# 06_-_Audio.net
KiCad netlist of a schematic drawn in Altium Designer
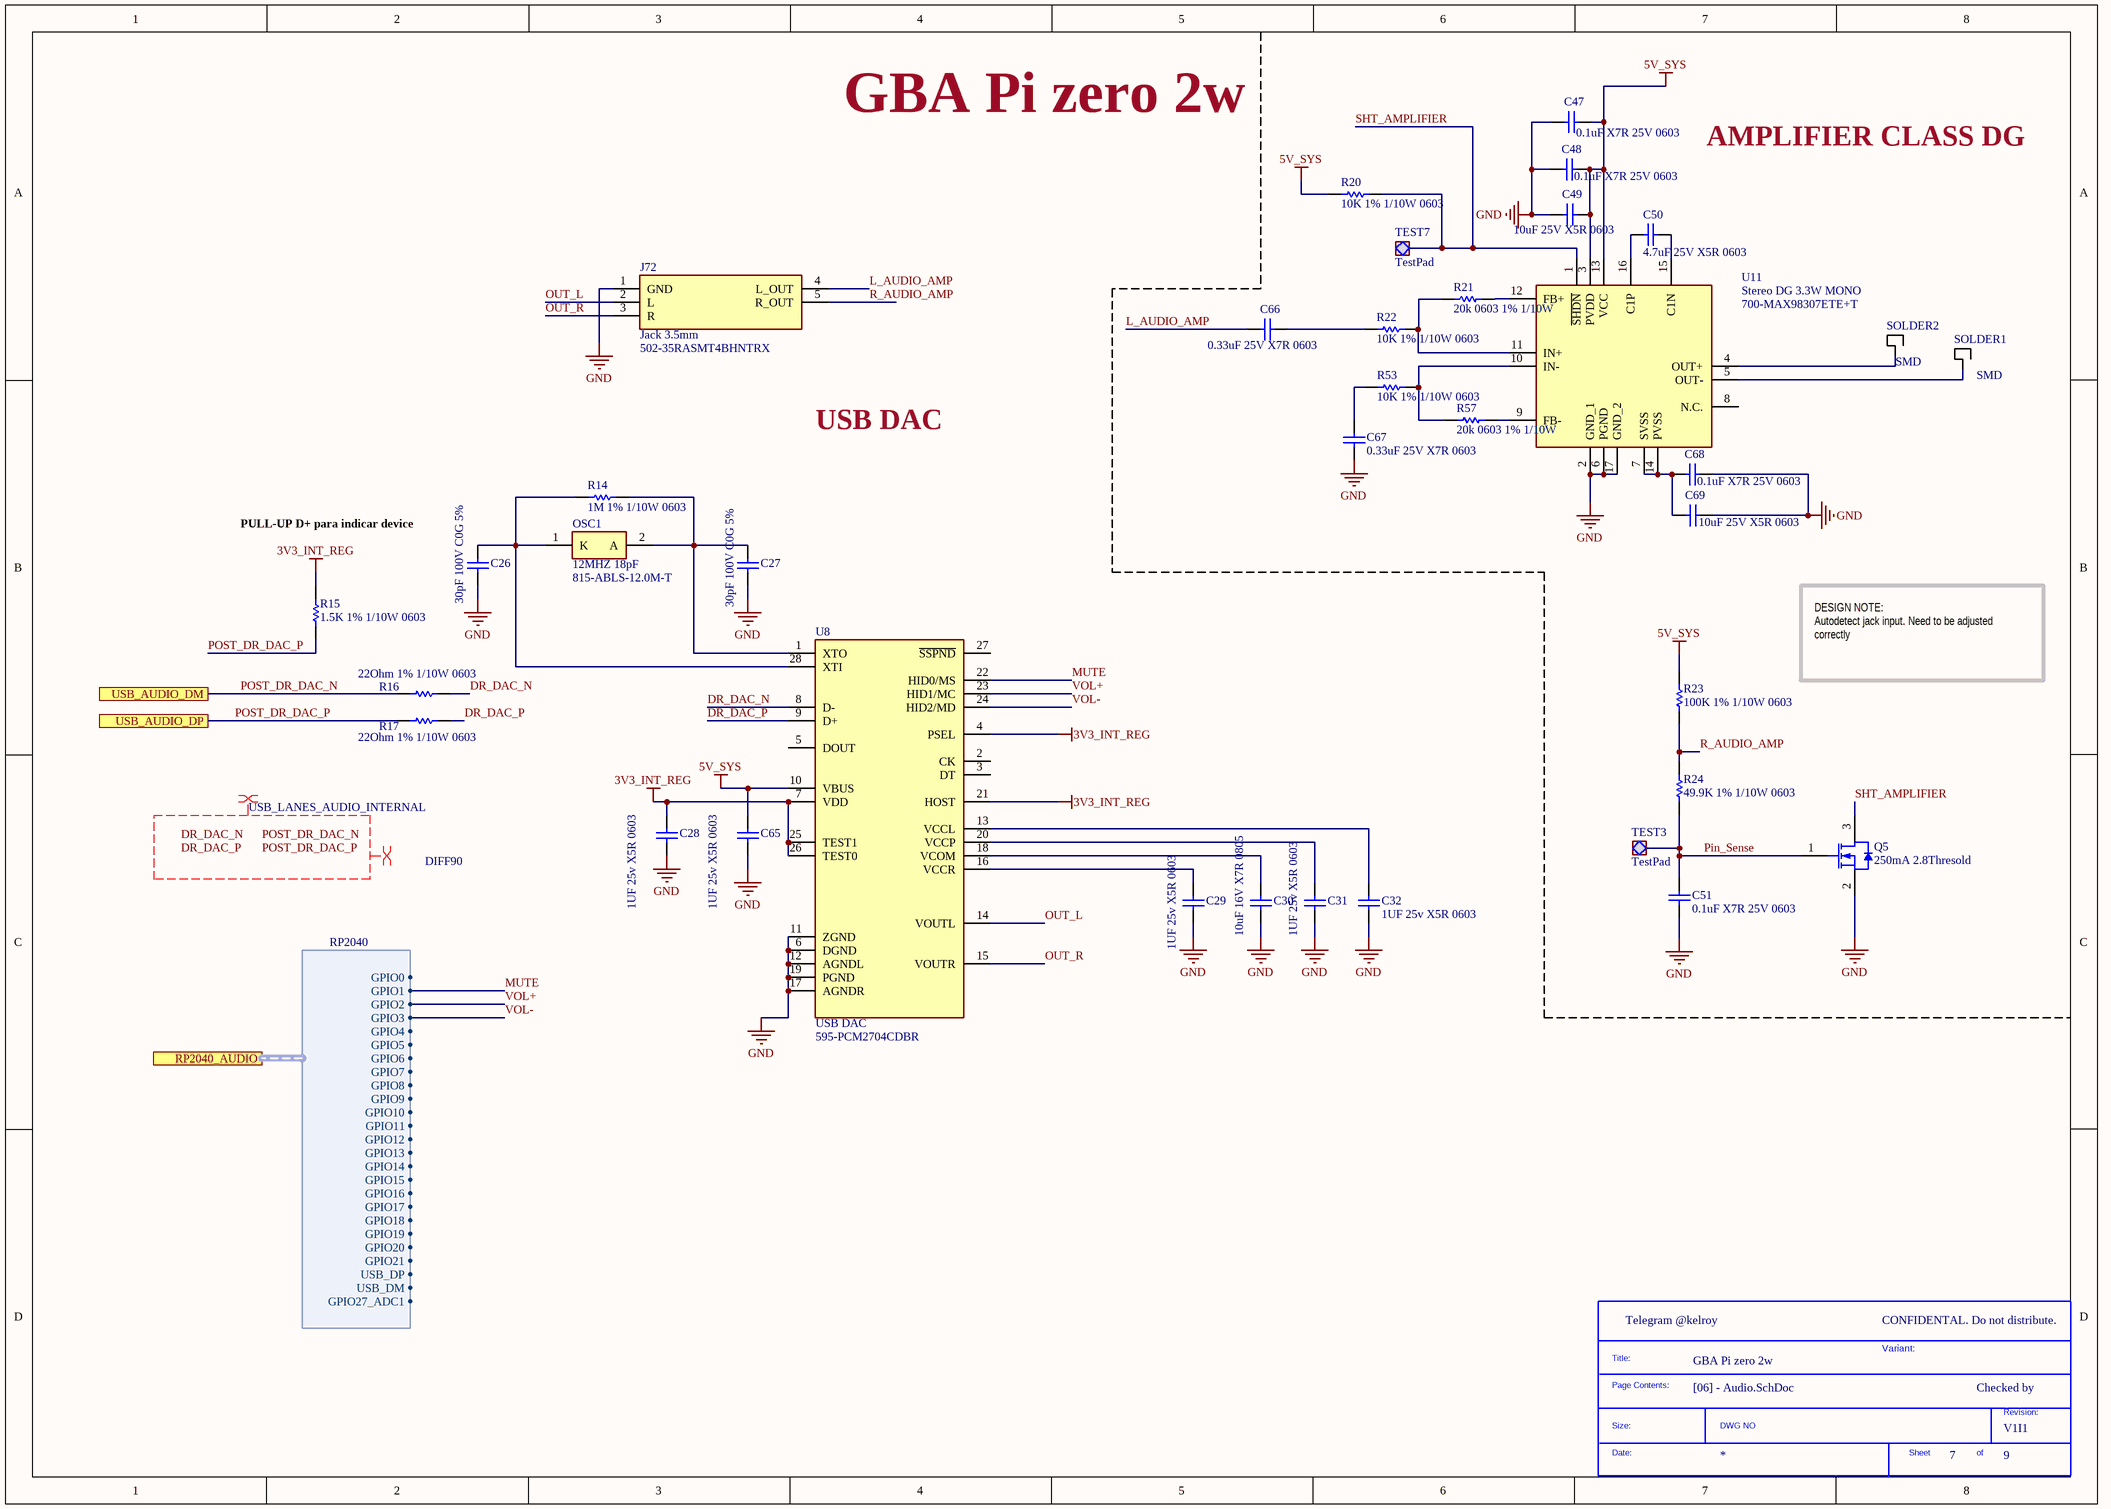
[diagram p0: [06] - Audio.SchDoc]

(export (version "E")
  (design (tool "Eeschema 10.0.6"))
  (components
    (comp (ref "C26")
      (value "30pF 100V C0G 5%")
      (footprint "C 0603/1608")
      (description "Condensadores de cerámica multicapa (MLCC- SMD/SMT) 30pF 100Volts C0G 5%")
      (fields
        (field (name "MANUFACTURER") "Murata")
        (field (name "MANUFACTURER PART NUMBER") "GCM1885C2A300JA16D")
      )
      (libsource (lib "LAN9514") (part "GCM1885C2A300JA16D"))
    )
    (comp (ref "C27")
      (value "30pF 100V C0G 5%")
      (footprint "C 0603/1608")
      (description "Condensadores de cerámica multicapa (MLCC- SMD/SMT) 30pF 100Volts C0G 5%")
      (fields
        (field (name "MANUFACTURER") "Murata")
        (field (name "MANUFACTURER PART NUMBER") "GCM1885C2A300JA16D")
      )
      (libsource (lib "LAN9514") (part "GCM1885C2A300JA16D"))
    )
    (comp (ref "C28")
      (value "1UF 25v X5R 0603")
      (footprint "C 0603/1608")
      (description "CAP CER 1UF 25V X5R 0603")
      (fields
        (field (name "MANUFACTURER") "Yageo")
        (field (name "MANUFACTURER PART NUMBER") "CC0603KRX5R8BB105")
      )
      (libsource (lib "CM3Board_V1I2") (part "CC0603KRX5R8BB105"))
    )
    (comp (ref "C29")
      (value "1UF 25v X5R 0603")
      (footprint "C 0603/1608")
      (description "CAP CER 1UF 25V X5R 0603")
      (fields
        (field (name "MANUFACTURER") "Yageo")
        (field (name "MANUFACTURER PART NUMBER") "CC0603KRX5R8BB105")
      )
      (libsource (lib "CM3Board_V1I2") (part "CC0603KRX5R8BB105"))
    )
    (comp (ref "C30")
      (value "10uF 16V X7R 0805")
      (footprint "C 0805/2012")
      (description "CAP CER 10UF 16V X7R 0805")
      (fields
        (field (name "MANUFACTURER") "Samsung Electro-Mechanics")
        (field (name "MANUFACTURER PART NUMBER") "CL21B106KOQNNNE")
      )
      (libsource (lib "CM3Board_V1I2") (part "CL21B106KOQNNNE"))
    )
    (comp (ref "C31")
      (value "1UF 25v X5R 0603")
      (footprint "C 0603/1608")
      (description "CAP CER 1UF 25V X5R 0603")
      (fields
        (field (name "MANUFACTURER") "Yageo")
        (field (name "MANUFACTURER PART NUMBER") "CC0603KRX5R8BB105")
      )
      (libsource (lib "CM3Board_V1I2") (part "CC0603KRX5R8BB105"))
    )
    (comp (ref "C32")
      (value "1UF 25v X5R 0603")
      (footprint "C 0603/1608")
      (description "CAP CER 1UF 25V X5R 0603")
      (fields
        (field (name "MANUFACTURER") "Yageo")
        (field (name "MANUFACTURER PART NUMBER") "CC0603KRX5R8BB105")
      )
      (libsource (lib "CM3Board_V1I2") (part "CC0603KRX5R8BB105"))
    )
    (comp (ref "C47")
      (value "0.1uF X7R 25V 0603")
      (footprint "C 0603/1608")
      (fields
        (field (name "MANUFACTURER") "Wurth Electronics")
        (field (name "MANUFACTURER PART NUMBER") "885012206071")
        (field (name "TOLERANCE") "10%")
      )
      (libsource (lib "altium-import") (part "root_2_885012206071_"))
    )
    (comp (ref "C48")
      (value "0.1uF X7R 25V 0603")
      (footprint "C 0603/1608")
      (fields
        (field (name "MANUFACTURER") "Wurth Electronics")
        (field (name "MANUFACTURER PART NUMBER") "885012206071")
        (field (name "TOLERANCE") "10%")
      )
      (libsource (lib "altium-import") (part "root_2_885012206071_"))
    )
    (comp (ref "C49")
      (value "10uF 25V X5R 0603")
      (footprint "C 0603/1608")
      (description "Cap Ceramic 10uF 25V X5R 10% SMD 0603 85°C Paper T/R")
      (libsource (lib "Kelboy") (part "GRM188R61E106KA73D"))
    )
    (comp (ref "C50")
      (value "4.7uF 25V X5R 0603")
      (footprint "C 0603/1608")
      (description "Condensadores de cerámica multicapa (MLCC- SMD/SMT) 0603 25VDC 4.7uF 20% X5R")
      (libsource (lib "Kelboy") (part "TMK107BBJ475MA-T"))
    )
    (comp (ref "C51")
      (value "0.1uF X7R 25V 0603")
      (footprint "C 0603/1608")
      (fields
        (field (name "MANUFACTURER") "Wurth Electronics")
        (field (name "MANUFACTURER PART NUMBER") "885012206071")
        (field (name "TOLERANCE") "10%")
      )
      (libsource (lib "altium-import") (part "root_1_885012206071_"))
    )
    (comp (ref "C65")
      (value "1UF 25v X5R 0603")
      (footprint "C 0603/1608")
      (description "CAP CER 1UF 25V X5R 0603")
      (fields
        (field (name "MANUFACTURER") "Yageo")
        (field (name "MANUFACTURER PART NUMBER") "CC0603KRX5R8BB105")
      )
      (libsource (lib "CM3Board_V1I2") (part "CC0603KRX5R8BB105"))
    )
    (comp (ref "C66")
      (value "0.33uF 25V X7R 0603")
      (footprint "C 0603/1608")
      (description "CAP CER 0.33UF 25V X7R 0603")
      (fields (field (name "TOLERANCE") "10%"))
      (libsource (lib "Kelboy") (part "885012206074"))
    )
    (comp (ref "C67")
      (value "0.33uF 25V X7R 0603")
      (footprint "C 0603/1608")
      (description "CAP CER 0.33UF 25V X7R 0603")
      (fields (field (name "TOLERANCE") "10%"))
      (libsource (lib "Kelboy") (part "885012206074"))
    )
    (comp (ref "C68")
      (value "0.1uF X7R 25V 0603")
      (footprint "C 0603/1608")
      (fields
        (field (name "MANUFACTURER") "Wurth Electronics")
        (field (name "MANUFACTURER PART NUMBER") "885012206071")
        (field (name "TOLERANCE") "10%")
      )
      (libsource (lib "altium-import") (part "root_2_885012206071_"))
    )
    (comp (ref "C69")
      (value "10uF 25V X5R 0603")
      (footprint "C 0603/1608")
      (description "Cap Ceramic 10uF 25V X5R 10% SMD 0603 85°C Paper T/R")
      (libsource (lib "Kelboy") (part "GRM188R61E106KA73D"))
    )
    (comp (ref "J72")
      (value "Jack 3.5mm")
      (footprint "35RASMT4BHNTRX")
      (description "SWC 35RASMT4BHNTRX Connectors > Audio - Video > Jacks (Audio) > 1/4 Audio Jacks")
      (fields
        (field (name "MANUFACTURER") "Switchcraft")
        (field (name "MANUFACTURER PART NUMBER") "35RASMT4BHNTRX")
        (field (name "SUPPLIER PART NUMBER 1") "502-35RASMT4BHNTRX")
      )
      (libsource (lib "GBA") (part "35RASMT4BHNTRX"))
    )
    (comp (ref "OSC1")
      (value "12MHZ 18pF")
      (footprint "HC/49US-(AT49)_1")
      (description "CRYSTAL 12.0000MHZ 18PF SMD")
      (fields
        (field (name "MANUFACTURER") "Abracon")
        (field (name "MANUFACTURER PART NUMBER") "ABLS-12.000MHZ-B4-T")
        (field (name "SUPPLIER PART NUMBER 1") "815-ABLS-12.0M-T")
      )
      (libsource (lib "CM3Board_V1I2") (part "ABLS-12.000MHZ-B4-T"))
    )
    (comp (ref "Q5")
      (value "250mA 2.8Thresold")
      (footprint "SOT-23-3")
      (description "MOSFET N-CH 60V 0.25A SST3")
      (fields (field (name "MANUFACTURER") "Rohm") (field (name "MANUFACTURER PART NUMBER") "RK7002BMT116"))
      (libsource (lib "ON_OFF_FastCharger") (part "RK7002BMT116"))
    )
    (comp (ref "R14")
      (value "1M 1% 1/10W 0603")
      (footprint "R 0603/1608")
      (description "RES SMD 1M OHM 1% 1/10W 0603")
      (fields (field (name "TOLERANCE") "1%"))
      (libsource (lib "CM3Board_V1I2") (part "RC0603FR-071ML"))
    )
    (comp (ref "R15")
      (value "1.5K 1% 1/10W 0603")
      (footprint "R 0603/1608")
      (description "RES SMD 1.5K OHM 1% 1/10W 0603")
      (fields
        (field (name "MANUFACTURER") "Yageo")
        (field (name "MANUFACTURER PART NUMBER") "RC0603FR-071K5L")
      )
      (libsource (lib "CM3Board_V1I2") (part "RC0603FR-071K5L"))
    )
    (comp (ref "R16")
      (value "22Ohm 1% 1/10W 0603")
      (footprint "R 0603/1608")
      (description "RES SMD 22 OHM 1% 1/10W 0603")
      (fields
        (field (name "MANUFACTURER") "Yageo")
        (field (name "MANUFACTURER PART NUMBER") "RC0603FR-0722RL")
      )
      (libsource (lib "CM3Board_V1I2") (part "RC0603FR-0722RL"))
    )
    (comp (ref "R17")
      (value "22Ohm 1% 1/10W 0603")
      (footprint "R 0603/1608")
      (description "RES SMD 22 OHM 1% 1/10W 0603")
      (fields
        (field (name "MANUFACTURER") "Yageo")
        (field (name "MANUFACTURER PART NUMBER") "RC0603FR-0722RL")
      )
      (libsource (lib "CM3Board_V1I2") (part "RC0603FR-0722RL"))
    )
    (comp (ref "R20")
      (value "10K 1% 1/10W 0603")
      (footprint "R 0603/1608")
      (description "RES SMD 10K OHM 1% 1/10W 0603")
      (fields
        (field (name "MANUFACTURER") "Yageo")
        (field (name "MANUFACTURER PART NUMBER") "RC0603FR-0710KL")
      )
      (libsource (lib "altium-import") (part "root_2_RC0603FR-0710KL_"))
    )
    (comp (ref "R21")
      (value "20k 0603 1% 1/10W")
      (footprint "R 0603/1608")
      (description "RES SMD 20K OHM 1% 1/10W 0603")
      (fields (field (name "TOLERANCE") "1%"))
      (libsource (lib "Kelboy") (part "RC0603FR-0720KL"))
    )
    (comp (ref "R22")
      (value "10K 1% 1/10W 0603")
      (footprint "R 0603/1608")
      (description "RES SMD 10K OHM 1% 1/10W 0603")
      (fields
        (field (name "MANUFACTURER") "Yageo")
        (field (name "MANUFACTURER PART NUMBER") "RC0603FR-0710KL")
      )
      (libsource (lib "altium-import") (part "root_2_RC0603FR-0710KL_"))
    )
    (comp (ref "R23")
      (value "100K 1% 1/10W 0603")
      (footprint "R 0603/1608")
      (description "RES SMD 100K OHM 1% 1/10W 0603")
      (fields
        (field (name "MANUFACTURER") "Yageo")
        (field (name "MANUFACTURER PART NUMBER") "RC0603FR-07100KL")
      )
      (libsource (lib "CM3Board_V1I2") (part "RC0603FR-07100KL"))
    )
    (comp (ref "R24")
      (value "49.9K 1% 1/10W 0603")
      (footprint "R 0603/1608")
      (description "RES SMD 49.9K OHM 1% 1/10W 0603")
      (fields
        (field (name "MANUFACTURER") "Yageo")
        (field (name "MANUFACTURER PART NUMBER") "RC0603FR-0749K9L")
      )
      (libsource (lib "CM3Board_V1I2") (part "RC0603FR-0749K9L"))
    )
    (comp (ref "R53")
      (value "10K 1% 1/10W 0603")
      (footprint "R 0603/1608")
      (description "RES SMD 10K OHM 1% 1/10W 0603")
      (fields
        (field (name "MANUFACTURER") "Yageo")
        (field (name "MANUFACTURER PART NUMBER") "RC0603FR-0710KL")
      )
      (libsource (lib "altium-import") (part "root_2_RC0603FR-0710KL_"))
    )
    (comp (ref "R57")
      (value "20k 0603 1% 1/10W")
      (footprint "R 0603/1608")
      (description "RES SMD 20K OHM 1% 1/10W 0603")
      (fields (field (name "TOLERANCE") "1%"))
      (libsource (lib "Kelboy") (part "RC0603FR-0720KL"))
    )
    (comp (ref "SOLDER1")
      (value "SMD")
      (footprint "SolderPAD")
      (libsource (lib "CM3Board_V1I2") (part "SOLDERPAD"))
    )
    (comp (ref "SOLDER2")
      (value "SMD")
      (footprint "SolderPAD")
      (libsource (lib "CM3Board_V1I2") (part "SOLDERPAD"))
    )
    (comp (ref "TEST3")
      (value "TestPad")
      (footprint "TestPad")
      (description "Probe Pad, SMT, ROUND, 2.0MM")
      (libsource (lib "CM3Board") (part "PP_SMT_ROUND_2MM"))
    )
    (comp (ref "TEST7")
      (value "TestPad")
      (footprint "TestPad")
      (description "Probe Pad, SMT, ROUND, 2.0MM")
      (libsource (lib "CM3Board") (part "PP_SMT_ROUND_2MM"))
    )
    (comp (ref "U8")
      (value "USB DAC")
      (footprint "SOP65P780X200-28N")
      (description "PCM2704C 98DB Snr Stereo Full Sp")
      (fields
        (field (name "MANUFACTURER") "Texas Instruments")
        (field (name "MANUFACTURER PART NUMBER") "PCM2704CDBR")
        (field (name "SUPPLIER PART NUMBER 1") "595-PCM2704CDBR")
      )
      (libsource (lib "GBA") (part "PCM2704CDBR"))
    )
    (comp (ref "U11")
      (value "Stereo DG 3.3W MONO")
      (footprint "QFN50P300X300X80-17N")
      (description "IC AMP AUD 3.3W MONO DG 16TQFN")
      (fields (field (name "SUPPLIER PART NUMBER 1") "700-MAX98307ETE+T"))
      (libsource (lib "Kelboy") (part "MAX98307ETE+T"))
    )
  )
  (nets
    (net (code "2") (name "/DR_DAC_N") (class "Default")
      (node (ref "R16") (pin "2") (pinfunction "2_2") (pintype "passive"))
      (node (ref "U8") (pin "8") (pinfunction "D-_8") (pintype "passive"))
    )
    (net (code "3") (name "/DR_DAC_P") (class "Default")
      (node (ref "R17") (pin "2") (pinfunction "2_2") (pintype "passive"))
      (node (ref "U8") (pin "9") (pinfunction "D+_9") (pintype "passive"))
    )
    (net (code "4") (name "/L_AUDIO_AMP") (class "Default")
      (node (ref "C66") (pin "2") (pinfunction "2_2") (pintype "passive"))
      (node (ref "J72") (pin "4") (pinfunction "L_OUT_4") (pintype "passive"))
    )
    (net (code "5") (name "/MUTE") (class "Default")
      (node (ref "U8") (pin "22") (pinfunction "HID0/MS_22") (pintype "passive"))
    )
    (net (code "6") (name "/OUT_L") (class "Default")
      (node (ref "J72") (pin "2") (pinfunction "L_2") (pintype "passive"))
      (node (ref "U8") (pin "14") (pinfunction "VOUTL_14") (pintype "passive"))
    )
    (net (code "7") (name "/OUT_R") (class "Default")
      (node (ref "J72") (pin "3") (pinfunction "R_3") (pintype "passive"))
      (node (ref "U8") (pin "15") (pinfunction "VOUTR_15") (pintype "passive"))
    )
    (net (code "8") (name "/POST_DR_DAC_N") (class "Default")
      (node (ref "R16") (pin "1") (pinfunction "1_1") (pintype "passive"))
    )
    (net (code "9") (name "/POST_DR_DAC_P") (class "Default")
      (node (ref "R15") (pin "2") (pinfunction "2_2") (pintype "passive"))
      (node (ref "R17") (pin "1") (pinfunction "1_1") (pintype "passive"))
    )
    (net (code "10") (name "/Pin_Sense") (class "Default")
      (node (ref "C51") (pin "1") (pinfunction "1_1") (pintype "passive"))
      (node (ref "Q5") (pin "1") (pinfunction "G_1") (pintype "passive"))
      (node (ref "R24") (pin "1") (pinfunction "1_1") (pintype "passive"))
      (node (ref "TEST3") (pin "1") (pinfunction "1_1") (pintype "passive"))
    )
    (net (code "11") (name "/R_AUDIO_AMP") (class "Default")
      (node (ref "J72") (pin "5") (pinfunction "R_OUT_5") (pintype "passive"))
      (node (ref "R23") (pin "1") (pinfunction "1_1") (pintype "passive"))
      (node (ref "R24") (pin "2") (pinfunction "2_2") (pintype "passive"))
    )
    (net (code "12") (name "/SHT_AMPLIFIER") (class "Default")
      (node (ref "Q5") (pin "3") (pinfunction "D_3") (pintype "passive"))
      (node (ref "R20") (pin "1") (pinfunction "1_1") (pintype "passive"))
      (node (ref "TEST7") (pin "1") (pinfunction "1_1") (pintype "passive"))
      (node (ref "U11") (pin "1") (pinfunction "~{SHDN}_1") (pintype "passive"))
    )
    (net (code "13") (name "/VOL+") (class "Default")
      (node (ref "U8") (pin "23") (pinfunction "HID1/MC_23") (pintype "passive"))
    )
    (net (code "14") (name "/VOL-") (class "Default")
      (node (ref "U8") (pin "24") (pinfunction "HID2/MD_24") (pintype "passive"))
    )
    (net (code "16") (name "3V3_INT_REG") (class "Default")
      (node (ref "C28") (pin "1") (pinfunction "1_1") (pintype "passive"))
      (node (ref "R15") (pin "1") (pinfunction "1_1") (pintype "passive"))
      (node (ref "U8") (pin "21") (pinfunction "HOST_21") (pintype "passive"))
      (node (ref "U8") (pin "25") (pinfunction "TEST1_25") (pintype "passive"))
      (node (ref "U8") (pin "26") (pinfunction "TEST0_26") (pintype "passive"))
      (node (ref "U8") (pin "4") (pinfunction "PSEL_4") (pintype "passive"))
      (node (ref "U8") (pin "7") (pinfunction "VDD_7") (pintype "passive"))
    )
    (net (code "17") (name "5V_SYS") (class "Default")
      (node (ref "C47") (pin "2") (pinfunction "2_2") (pintype "passive"))
      (node (ref "C48") (pin "2") (pinfunction "2_2") (pintype "passive"))
      (node (ref "C49") (pin "2") (pinfunction "2_2") (pintype "passive"))
      (node (ref "C65") (pin "1") (pinfunction "1_1") (pintype "passive"))
      (node (ref "R20") (pin "2") (pinfunction "2_2") (pintype "passive"))
      (node (ref "R23") (pin "2") (pinfunction "2_2") (pintype "passive"))
      (node (ref "U11") (pin "13") (pinfunction "VCC_13") (pintype "passive"))
      (node (ref "U11") (pin "3") (pinfunction "PVDD_3") (pintype "passive"))
      (node (ref "U8") (pin "10") (pinfunction "VBUS_10") (pintype "passive"))
    )
    (net (code "18") (name "GND") (class "Default")
      (node (ref "C26") (pin "2") (pinfunction "2_2") (pintype "passive"))
      (node (ref "C27") (pin "2") (pinfunction "2_2") (pintype "passive"))
      (node (ref "C28") (pin "2") (pinfunction "2_2") (pintype "passive"))
      (node (ref "C29") (pin "1") (pinfunction "1_1") (pintype "passive"))
      (node (ref "C30") (pin "2") (pinfunction "2_2") (pintype "passive"))
      (node (ref "C31") (pin "1") (pinfunction "1_1") (pintype "passive"))
      (node (ref "C32") (pin "1") (pinfunction "1_1") (pintype "passive"))
      (node (ref "C47") (pin "1") (pinfunction "1_1") (pintype "passive"))
      (node (ref "C48") (pin "1") (pinfunction "1_1") (pintype "passive"))
      (node (ref "C49") (pin "1") (pinfunction "1_1") (pintype "passive"))
      (node (ref "C51") (pin "2") (pinfunction "2_2") (pintype "passive"))
      (node (ref "C65") (pin "2") (pinfunction "2_2") (pintype "passive"))
      (node (ref "C67") (pin "2") (pinfunction "2_2") (pintype "passive"))
      (node (ref "C68") (pin "2") (pinfunction "2_2") (pintype "passive"))
      (node (ref "C69") (pin "2") (pinfunction "2_2") (pintype "passive"))
      (node (ref "J72") (pin "1") (pinfunction "GND_1") (pintype "passive"))
      (node (ref "Q5") (pin "2") (pinfunction "S_2") (pintype "passive"))
      (node (ref "U11") (pin "17") (pinfunction "GND_2_17") (pintype "passive"))
      (node (ref "U11") (pin "2") (pinfunction "GND_1_2") (pintype "passive"))
      (node (ref "U11") (pin "6") (pinfunction "PGND_6") (pintype "passive"))
      (node (ref "U8") (pin "11") (pinfunction "ZGND_11") (pintype "passive"))
      (node (ref "U8") (pin "12") (pinfunction "AGNDL_12") (pintype "passive"))
      (node (ref "U8") (pin "17") (pinfunction "AGNDR_17") (pintype "passive"))
      (node (ref "U8") (pin "19") (pinfunction "PGND_19") (pintype "passive"))
      (node (ref "U8") (pin "6") (pinfunction "DGND_6") (pintype "passive"))
    )
    (net (code "19") (name "Net-(C66-Pad1)") (class "Default")
      (node (ref "C66") (pin "1") (pinfunction "1_1") (pintype "passive"))
      (node (ref "R22") (pin "2") (pinfunction "2_2") (pintype "passive"))
    )
    (net (code "20") (name "Net-(C67-Pad1)") (class "Default")
      (node (ref "C67") (pin "1") (pinfunction "1_1") (pintype "passive"))
      (node (ref "R53") (pin "2") (pinfunction "2_2") (pintype "passive"))
    )
    (net (code "21") (name "Net-(OSC1-A)") (class "Default")
      (node (ref "C27") (pin "1") (pinfunction "1_1") (pintype "passive"))
      (node (ref "OSC1") (pin "2") (pinfunction "A_2") (pintype "passive"))
      (node (ref "R14") (pin "2") (pinfunction "2_2") (pintype "passive"))
      (node (ref "U8") (pin "1") (pinfunction "XTO_1") (pintype "passive"))
    )
    (net (code "22") (name "Net-(OSC1-K)") (class "Default")
      (node (ref "C26") (pin "1") (pinfunction "1_1") (pintype "passive"))
      (node (ref "OSC1") (pin "1") (pinfunction "K_1") (pintype "passive"))
      (node (ref "R14") (pin "1") (pinfunction "1_1") (pintype "passive"))
      (node (ref "U8") (pin "28") (pinfunction "XTI_28") (pintype "passive"))
    )
    (net (code "23") (name "Net-(U8-VCCL)") (class "Default")
      (node (ref "C32") (pin "2") (pinfunction "2_2") (pintype "passive"))
      (node (ref "U8") (pin "13") (pinfunction "VCCL_13") (pintype "passive"))
    )
    (net (code "24") (name "Net-(U8-VCCP)") (class "Default")
      (node (ref "C31") (pin "2") (pinfunction "2_2") (pintype "passive"))
      (node (ref "U8") (pin "20") (pinfunction "VCCP_20") (pintype "passive"))
    )
    (net (code "25") (name "Net-(U8-VCCR)") (class "Default")
      (node (ref "C29") (pin "2") (pinfunction "2_2") (pintype "passive"))
      (node (ref "U8") (pin "16") (pinfunction "VCCR_16") (pintype "passive"))
    )
    (net (code "26") (name "Net-(U8-VCOM)") (class "Default")
      (node (ref "C30") (pin "1") (pinfunction "1_1") (pintype "passive"))
      (node (ref "U8") (pin "18") (pinfunction "VCOM_18") (pintype "passive"))
    )
    (net (code "27") (name "Net-(U11-C1N)") (class "Default")
      (node (ref "C50") (pin "2") (pinfunction "2_2") (pintype "passive"))
      (node (ref "U11") (pin "15") (pinfunction "C1N_15") (pintype "passive"))
    )
    (net (code "28") (name "Net-(U11-C1P)") (class "Default")
      (node (ref "C50") (pin "1") (pinfunction "1_1") (pintype "passive"))
      (node (ref "U11") (pin "16") (pinfunction "C1P_16") (pintype "passive"))
    )
    (net (code "29") (name "Net-(U11-FB+)") (class "Default")
      (node (ref "R21") (pin "2") (pinfunction "2_2") (pintype "passive"))
      (node (ref "U11") (pin "12") (pinfunction "FB+_12") (pintype "passive"))
    )
    (net (code "30") (name "Net-(U11-FB-)") (class "Default")
      (node (ref "R57") (pin "2") (pinfunction "2_2") (pintype "passive"))
      (node (ref "U11") (pin "9") (pinfunction "FB-_9") (pintype "passive"))
    )
    (net (code "31") (name "Net-(U11-IN+)") (class "Default")
      (node (ref "R21") (pin "1") (pinfunction "1_1") (pintype "passive"))
      (node (ref "R22") (pin "1") (pinfunction "1_1") (pintype "passive"))
      (node (ref "U11") (pin "11") (pinfunction "IN+_11") (pintype "passive"))
    )
    (net (code "32") (name "Net-(U11-IN-)") (class "Default")
      (node (ref "R53") (pin "1") (pinfunction "1_1") (pintype "passive"))
      (node (ref "R57") (pin "1") (pinfunction "1_1") (pintype "passive"))
      (node (ref "U11") (pin "10") (pinfunction "IN-_10") (pintype "passive"))
    )
    (net (code "33") (name "Net-(U11-OUT+)") (class "Default")
      (node (ref "SOLDER2") (pin "1") (pinfunction "1_1") (pintype "passive"))
      (node (ref "U11") (pin "4") (pinfunction "OUT+_4") (pintype "passive"))
    )
    (net (code "34") (name "Net-(U11-OUT-)") (class "Default")
      (node (ref "SOLDER1") (pin "1") (pinfunction "1_1") (pintype "passive"))
      (node (ref "U11") (pin "5") (pinfunction "OUT-_5") (pintype "passive"))
    )
    (net (code "35") (name "Net-(U11-PVSS)") (class "Default")
      (node (ref "C68") (pin "1") (pinfunction "1_1") (pintype "passive"))
      (node (ref "C69") (pin "1") (pinfunction "1_1") (pintype "passive"))
      (node (ref "U11") (pin "14") (pinfunction "PVSS_14") (pintype "passive"))
      (node (ref "U11") (pin "7") (pinfunction "SVSS_7") (pintype "passive"))
    )
    (net (code "36") (name "unconnected-(U8-CK-Pad2)") (class "Default")
      (node (ref "U8") (pin "2") (pinfunction "CK_2") (pintype "passive"))
    )
    (net (code "37") (name "unconnected-(U8-DOUT-Pad5)") (class "Default")
      (node (ref "U8") (pin "5") (pinfunction "DOUT_5") (pintype "passive"))
    )
    (net (code "38") (name "unconnected-(U8-DT-Pad3)") (class "Default")
      (node (ref "U8") (pin "3") (pinfunction "DT_3") (pintype "passive"))
    )
    (net (code "39") (name "unconnected-(U8-~{SSPND}-Pad27)") (class "Default")
      (node (ref "U8") (pin "27") (pinfunction "~{SSPND}_27") (pintype "passive"))
    )
    (net (code "40") (name "unconnected-(U11-N.C.-Pad8)") (class "Default")
      (node (ref "U11") (pin "8") (pinfunction "N.C._8") (pintype "passive"))
    )
  )
)
